# Head_Sensors.net
KiCad netlist of a schematic drawn in Altium Designer
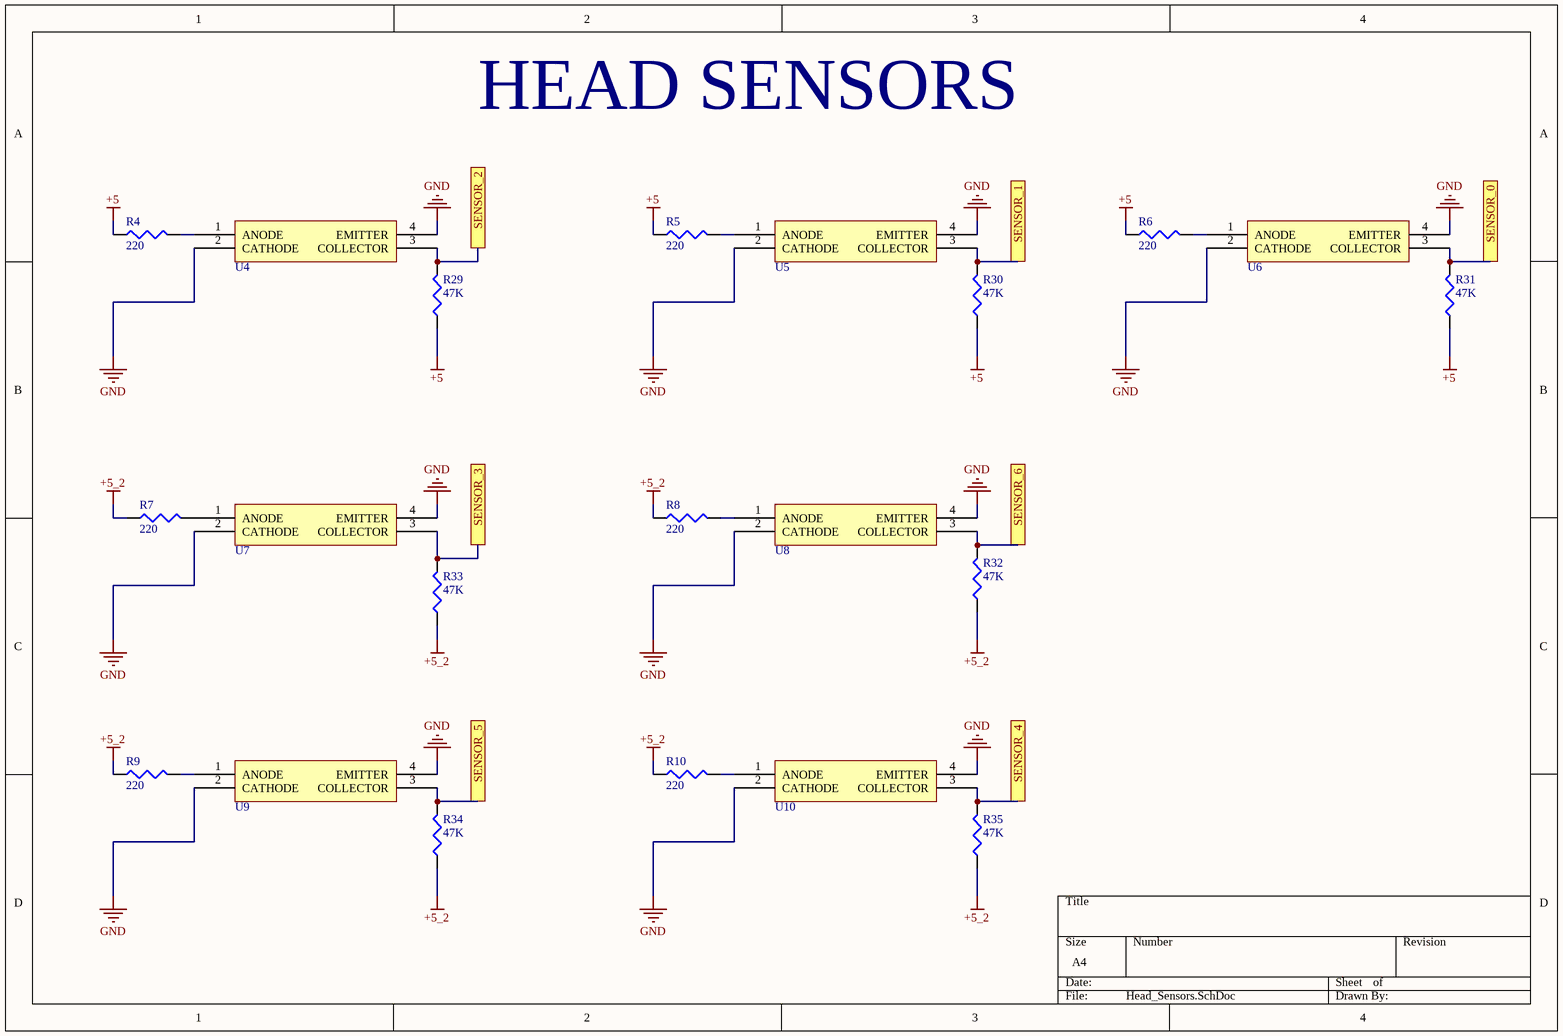
[diagram p0: Head_Sensors.SchDoc]

(export (version "E")
  (design (tool "Eeschema 10.0.6"))
  (components
    (comp (ref "R4")
      (value "220")
      (footprint "6-0805_M")
      (description "RES SMD 220 OHM 1% 1/8W 0805")
      (fields
        (field (name "MANUFACTURER") "Vishay Semiconductors")
        (field (name "MANUFACTURER PART NUMBER") "CRCW0805220RFKEAC")
      )
      (libsource (lib "BiricuticoBonito") (part "Resistor 220 0805"))
    )
    (comp (ref "R5")
      (value "220")
      (footprint "6-0805_M")
      (description "RES SMD 220 OHM 1% 1/8W 0805")
      (fields
        (field (name "MANUFACTURER") "Vishay Semiconductors")
        (field (name "MANUFACTURER PART NUMBER") "CRCW0805220RFKEAC")
      )
      (libsource (lib "BiricuticoBonito") (part "Resistor 220 0805"))
    )
    (comp (ref "R6")
      (value "220")
      (footprint "6-0805_M")
      (description "RES SMD 220 OHM 1% 1/8W 0805")
      (fields
        (field (name "MANUFACTURER") "Vishay Semiconductors")
        (field (name "MANUFACTURER PART NUMBER") "CRCW0805220RFKEAC")
      )
      (libsource (lib "BiricuticoBonito") (part "Resistor 220 0805"))
    )
    (comp (ref "R7")
      (value "220")
      (footprint "6-0805_M")
      (description "RES SMD 220 OHM 1% 1/8W 0805")
      (fields
        (field (name "MANUFACTURER") "Vishay Semiconductors")
        (field (name "MANUFACTURER PART NUMBER") "CRCW0805220RFKEAC")
      )
      (libsource (lib "BiricuticoBonito") (part "Resistor 220 0805"))
    )
    (comp (ref "R8")
      (value "220")
      (footprint "6-0805_M")
      (description "RES SMD 220 OHM 1% 1/8W 0805")
      (fields
        (field (name "MANUFACTURER") "Vishay Semiconductors")
        (field (name "MANUFACTURER PART NUMBER") "CRCW0805220RFKEAC")
      )
      (libsource (lib "BiricuticoBonito") (part "Resistor 220 0805"))
    )
    (comp (ref "R9")
      (value "220")
      (footprint "6-0805_M")
      (description "RES SMD 220 OHM 1% 1/8W 0805")
      (fields
        (field (name "MANUFACTURER") "Vishay Semiconductors")
        (field (name "MANUFACTURER PART NUMBER") "CRCW0805220RFKEAC")
      )
      (libsource (lib "BiricuticoBonito") (part "Resistor 220 0805"))
    )
    (comp (ref "R10")
      (value "220")
      (footprint "6-0805_M")
      (description "RES SMD 220 OHM 1% 1/8W 0805")
      (fields
        (field (name "MANUFACTURER") "Vishay Semiconductors")
        (field (name "MANUFACTURER PART NUMBER") "CRCW0805220RFKEAC")
      )
      (libsource (lib "BiricuticoBonito") (part "Resistor 220 0805"))
    )
    (comp (ref "R29")
      (value "47K")
      (footprint "6-0805_M")
      (description "RES SMD 47K OHM 1% 1/8W 0805")
      (fields
        (field (name "MANUFACTURER") "Vishay")
        (field (name "MANUFACTURER PART NUMBER") "CRCW080547K0FKEA")
      )
      (libsource (lib "BiricuticoBonito") (part "Resistor 47K 0805"))
    )
    (comp (ref "R30")
      (value "47K")
      (footprint "6-0805_M")
      (description "RES SMD 47K OHM 1% 1/8W 0805")
      (fields
        (field (name "MANUFACTURER") "Vishay")
        (field (name "MANUFACTURER PART NUMBER") "CRCW080547K0FKEA")
      )
      (libsource (lib "BiricuticoBonito") (part "Resistor 47K 0805"))
    )
    (comp (ref "R31")
      (value "47K")
      (footprint "6-0805_M")
      (description "RES SMD 47K OHM 1% 1/8W 0805")
      (fields
        (field (name "MANUFACTURER") "Vishay")
        (field (name "MANUFACTURER PART NUMBER") "CRCW080547K0FKEA")
      )
      (libsource (lib "BiricuticoBonito") (part "Resistor 47K 0805"))
    )
    (comp (ref "R32")
      (value "47K")
      (footprint "6-0805_M")
      (description "RES SMD 47K OHM 1% 1/8W 0805")
      (fields
        (field (name "MANUFACTURER") "Vishay")
        (field (name "MANUFACTURER PART NUMBER") "CRCW080547K0FKEA")
      )
      (libsource (lib "BiricuticoBonito") (part "Resistor 47K 0805"))
    )
    (comp (ref "R33")
      (value "47K")
      (footprint "6-0805_M")
      (description "RES SMD 47K OHM 1% 1/8W 0805")
      (fields
        (field (name "MANUFACTURER") "Vishay")
        (field (name "MANUFACTURER PART NUMBER") "CRCW080547K0FKEA")
      )
      (libsource (lib "BiricuticoBonito") (part "Resistor 47K 0805"))
    )
    (comp (ref "R34")
      (value "47K")
      (footprint "6-0805_M")
      (description "RES SMD 47K OHM 1% 1/8W 0805")
      (fields
        (field (name "MANUFACTURER") "Vishay")
        (field (name "MANUFACTURER PART NUMBER") "CRCW080547K0FKEA")
      )
      (libsource (lib "BiricuticoBonito") (part "Resistor 47K 0805"))
    )
    (comp (ref "R35")
      (value "47K")
      (footprint "6-0805_M")
      (description "RES SMD 47K OHM 1% 1/8W 0805")
      (fields
        (field (name "MANUFACTURER") "Vishay")
        (field (name "MANUFACTURER PART NUMBER") "CRCW080547K0FKEA")
      )
      (libsource (lib "BiricuticoBonito") (part "Resistor 47K 0805"))
    )
    (comp (ref "U4")
      (value "Optical Switches")
      (footprint "QRE1113GR")
      (description "SENSOR OPTO TRANS REFL SMD PHOTO")
      (fields
        (field (name "MANUFACTURER") "ON Semiconductor / Fairchild")
        (field (name "MANUFACTURER PART NUMBER") "QRE1113GR")
      )
      (libsource (lib "BiricuticoBonito") (part "Optical Switches"))
    )
    (comp (ref "U5")
      (value "Optical Switches")
      (footprint "QRE1113GR")
      (description "SENSOR OPTO TRANS REFL SMD PHOTO")
      (fields
        (field (name "MANUFACTURER") "ON Semiconductor / Fairchild")
        (field (name "MANUFACTURER PART NUMBER") "QRE1113GR")
      )
      (libsource (lib "BiricuticoBonito") (part "Optical Switches"))
    )
    (comp (ref "U6")
      (value "Optical Switches")
      (footprint "QRE1113GR")
      (description "SENSOR OPTO TRANS REFL SMD PHOTO")
      (fields
        (field (name "MANUFACTURER") "ON Semiconductor / Fairchild")
        (field (name "MANUFACTURER PART NUMBER") "QRE1113GR")
      )
      (libsource (lib "BiricuticoBonito") (part "Optical Switches"))
    )
    (comp (ref "U7")
      (value "Optical Switches")
      (footprint "QRE1113GR")
      (description "SENSOR OPTO TRANS REFL SMD PHOTO")
      (fields
        (field (name "MANUFACTURER") "ON Semiconductor / Fairchild")
        (field (name "MANUFACTURER PART NUMBER") "QRE1113GR")
      )
      (libsource (lib "BiricuticoBonito") (part "Optical Switches"))
    )
    (comp (ref "U8")
      (value "Optical Switches")
      (footprint "QRE1113GR")
      (description "SENSOR OPTO TRANS REFL SMD PHOTO")
      (fields
        (field (name "MANUFACTURER") "ON Semiconductor / Fairchild")
        (field (name "MANUFACTURER PART NUMBER") "QRE1113GR")
      )
      (libsource (lib "BiricuticoBonito") (part "Optical Switches"))
    )
    (comp (ref "U9")
      (value "Optical Switches")
      (footprint "QRE1113GR")
      (description "SENSOR OPTO TRANS REFL SMD PHOTO")
      (fields
        (field (name "MANUFACTURER") "ON Semiconductor / Fairchild")
        (field (name "MANUFACTURER PART NUMBER") "QRE1113GR")
      )
      (libsource (lib "BiricuticoBonito") (part "Optical Switches"))
    )
    (comp (ref "U10")
      (value "Optical Switches")
      (footprint "QRE1113GR")
      (description "SENSOR OPTO TRANS REFL SMD PHOTO")
      (fields
        (field (name "MANUFACTURER") "ON Semiconductor / Fairchild")
        (field (name "MANUFACTURER PART NUMBER") "QRE1113GR")
      )
      (libsource (lib "BiricuticoBonito") (part "Optical Switches"))
    )
  )
  (nets
    (net (code "1") (name "+5") (class "Default")
      (node (ref "R29") (pin "1") (pinfunction "28_1") (pintype "passive"))
      (node (ref "R30") (pin "1") (pinfunction "28_1") (pintype "passive"))
      (node (ref "R31") (pin "1") (pinfunction "28_1") (pintype "passive"))
      (node (ref "R4") (pin "1") (pinfunction "28_1") (pintype "passive"))
      (node (ref "R5") (pin "1") (pinfunction "28_1") (pintype "passive"))
      (node (ref "R6") (pin "1") (pinfunction "28_1") (pintype "passive"))
    )
    (net (code "2") (name "+5_2") (class "Default")
      (node (ref "R10") (pin "1") (pinfunction "28_1") (pintype "passive"))
      (node (ref "R32") (pin "1") (pinfunction "28_1") (pintype "passive"))
      (node (ref "R33") (pin "1") (pinfunction "28_1") (pintype "passive"))
      (node (ref "R34") (pin "1") (pinfunction "28_1") (pintype "passive"))
      (node (ref "R35") (pin "1") (pinfunction "28_1") (pintype "passive"))
      (node (ref "R7") (pin "1") (pinfunction "28_1") (pintype "passive"))
      (node (ref "R8") (pin "1") (pinfunction "28_1") (pintype "passive"))
      (node (ref "R9") (pin "1") (pinfunction "28_1") (pintype "passive"))
    )
    (net (code "3") (name "/SENSOR_0") (class "Default")
      (node (ref "R31") (pin "2") (pinfunction "27_2") (pintype "passive"))
      (node (ref "U6") (pin "3") (pinfunction "COLLECTOR_3") (pintype "passive"))
    )
    (net (code "4") (name "/SENSOR_1") (class "Default")
      (node (ref "R30") (pin "2") (pinfunction "27_2") (pintype "passive"))
      (node (ref "U5") (pin "3") (pinfunction "COLLECTOR_3") (pintype "passive"))
    )
    (net (code "5") (name "/SENSOR_2") (class "Default")
      (node (ref "R29") (pin "2") (pinfunction "27_2") (pintype "passive"))
      (node (ref "U4") (pin "3") (pinfunction "COLLECTOR_3") (pintype "passive"))
    )
    (net (code "6") (name "/SENSOR_3") (class "Default")
      (node (ref "R33") (pin "2") (pinfunction "27_2") (pintype "passive"))
      (node (ref "U7") (pin "3") (pinfunction "COLLECTOR_3") (pintype "passive"))
    )
    (net (code "7") (name "/SENSOR_4") (class "Default")
      (node (ref "R35") (pin "2") (pinfunction "27_2") (pintype "passive"))
      (node (ref "U10") (pin "3") (pinfunction "COLLECTOR_3") (pintype "passive"))
    )
    (net (code "8") (name "/SENSOR_5") (class "Default")
      (node (ref "R34") (pin "2") (pinfunction "27_2") (pintype "passive"))
      (node (ref "U9") (pin "3") (pinfunction "COLLECTOR_3") (pintype "passive"))
    )
    (net (code "9") (name "/SENSOR_6") (class "Default")
      (node (ref "R32") (pin "2") (pinfunction "27_2") (pintype "passive"))
      (node (ref "U8") (pin "3") (pinfunction "COLLECTOR_3") (pintype "passive"))
    )
    (net (code "10") (name "GND") (class "Default")
      (node (ref "U10") (pin "2") (pinfunction "CATHODE_2") (pintype "passive"))
      (node (ref "U10") (pin "4") (pinfunction "EMITTER_4") (pintype "passive"))
      (node (ref "U4") (pin "2") (pinfunction "CATHODE_2") (pintype "passive"))
      (node (ref "U4") (pin "4") (pinfunction "EMITTER_4") (pintype "passive"))
      (node (ref "U5") (pin "2") (pinfunction "CATHODE_2") (pintype "passive"))
      (node (ref "U5") (pin "4") (pinfunction "EMITTER_4") (pintype "passive"))
      (node (ref "U6") (pin "2") (pinfunction "CATHODE_2") (pintype "passive"))
      (node (ref "U6") (pin "4") (pinfunction "EMITTER_4") (pintype "passive"))
      (node (ref "U7") (pin "2") (pinfunction "CATHODE_2") (pintype "passive"))
      (node (ref "U7") (pin "4") (pinfunction "EMITTER_4") (pintype "passive"))
      (node (ref "U8") (pin "2") (pinfunction "CATHODE_2") (pintype "passive"))
      (node (ref "U8") (pin "4") (pinfunction "EMITTER_4") (pintype "passive"))
      (node (ref "U9") (pin "2") (pinfunction "CATHODE_2") (pintype "passive"))
      (node (ref "U9") (pin "4") (pinfunction "EMITTER_4") (pintype "passive"))
    )
    (net (code "11") (name "Net-(R4-27)") (class "Default")
      (node (ref "R4") (pin "2") (pinfunction "27_2") (pintype "passive"))
      (node (ref "U4") (pin "1") (pinfunction "ANODE_1") (pintype "passive"))
    )
    (net (code "12") (name "Net-(R5-27)") (class "Default")
      (node (ref "R5") (pin "2") (pinfunction "27_2") (pintype "passive"))
      (node (ref "U5") (pin "1") (pinfunction "ANODE_1") (pintype "passive"))
    )
    (net (code "13") (name "Net-(R6-27)") (class "Default")
      (node (ref "R6") (pin "2") (pinfunction "27_2") (pintype "passive"))
      (node (ref "U6") (pin "1") (pinfunction "ANODE_1") (pintype "passive"))
    )
    (net (code "14") (name "Net-(R7-27)") (class "Default")
      (node (ref "R7") (pin "2") (pinfunction "27_2") (pintype "passive"))
      (node (ref "U7") (pin "1") (pinfunction "ANODE_1") (pintype "passive"))
    )
    (net (code "15") (name "Net-(R8-27)") (class "Default")
      (node (ref "R8") (pin "2") (pinfunction "27_2") (pintype "passive"))
      (node (ref "U8") (pin "1") (pinfunction "ANODE_1") (pintype "passive"))
    )
    (net (code "16") (name "Net-(R9-27)") (class "Default")
      (node (ref "R9") (pin "2") (pinfunction "27_2") (pintype "passive"))
      (node (ref "U9") (pin "1") (pinfunction "ANODE_1") (pintype "passive"))
    )
    (net (code "17") (name "Net-(R10-27)") (class "Default")
      (node (ref "R10") (pin "2") (pinfunction "27_2") (pintype "passive"))
      (node (ref "U10") (pin "1") (pinfunction "ANODE_1") (pintype "passive"))
    )
  )
)
